# TinyDVR_Slave.net
KiCad netlist of a schematic drawn in Altium Designer
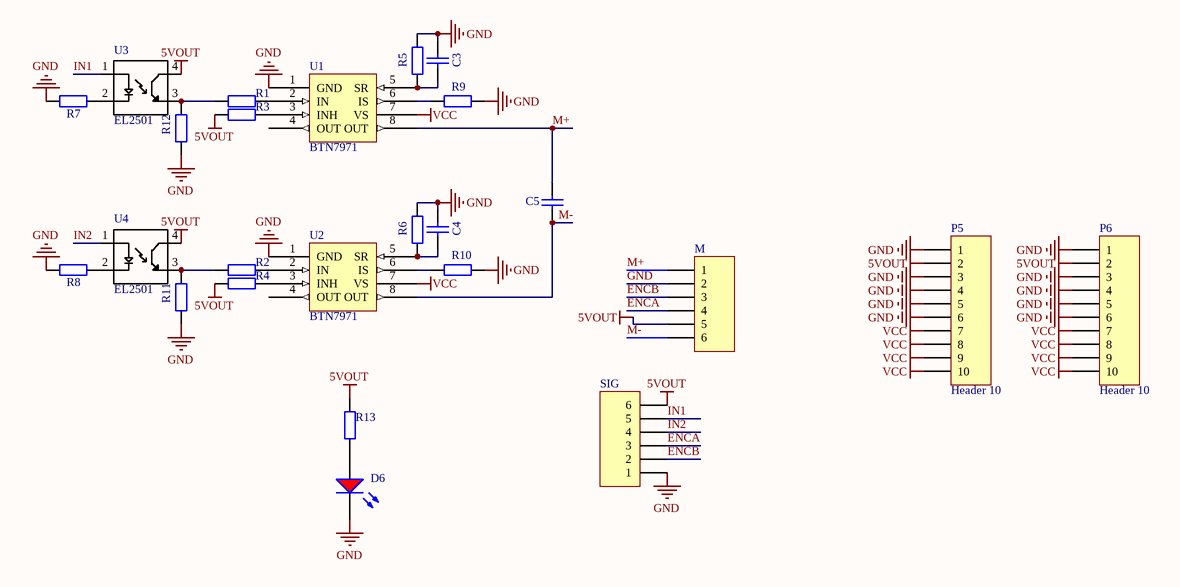
[diagram p0: TinyDVR_Slave.SchDoc]

(export (version "E")
  (design (tool "Eeschema 10.0.6"))
  (components
    (comp (ref "C3")
      (value "100nF (104) 10% 50V")
      (footprint "0603_C")
      (description "贴片电容")
      (libsource (lib "Miscellaneous Devices LC") (part "0603 100nF (104) 10% 50V"))
    )
    (comp (ref "C4")
      (value "100nF (104) 10% 50V")
      (footprint "0603_C")
      (description "贴片电容")
      (libsource (lib "Miscellaneous Devices LC") (part "0603 100nF (104) 10% 50V"))
    )
    (comp (ref "C5")
      (value "22pF (220) 5% 50V")
      (footprint "0603_C")
      (description "贴片电容")
      (libsource (lib "Miscellaneous Devices LC") (part "0603 22pF (220) 5% 50V"))
    )
    (comp (ref "D6")
      (value "红灯 0603")
      (footprint "0603_LED_S1")
      (description "发光二极管")
      (libsource (lib "Miscellaneous Devices LC") (part "0603 红灯"))
    )
    (comp (ref "M")
      (value "Header 6H")
      (footprint "HDR1X6H")
      (description "Header, 6-Pin, Right Angle")
      (fields (field (name "PUBLISHER") "Altium Limited"))
      (libsource (lib "Miscellaneous Connectors") (part "Header 6H"))
    )
    (comp (ref "P5")
      (value "Header 10")
      (footprint "HDR1X10")
      (description "Header, 10-Pin")
      (fields (field (name "PUBLISHER") "Altium Limited"))
      (libsource (lib "Miscellaneous Connectors") (part "Header 10"))
    )
    (comp (ref "P6")
      (value "Header 10")
      (footprint "HDR1X10")
      (description "Header, 10-Pin")
      (fields (field (name "PUBLISHER") "Altium Limited"))
      (libsource (lib "Miscellaneous Connectors") (part "Header 10"))
    )
    (comp (ref "R1")
      (value "10KΩ (1002) ±1%")
      (footprint "0603_R")
      (description "贴片电阻")
      (libsource (lib "Miscellaneous Devices LC") (part "0603 10KΩ (1002) 1%"))
    )
    (comp (ref "R2")
      (value "10KΩ (1002) ±1%")
      (footprint "0603_R")
      (description "贴片电阻")
      (libsource (lib "Miscellaneous Devices LC") (part "0603 10KΩ (1002) 1%"))
    )
    (comp (ref "R3")
      (value "10KΩ (1002) ±1%")
      (footprint "0603_R")
      (description "贴片电阻")
      (libsource (lib "Miscellaneous Devices LC") (part "0603 10KΩ (1002) 1%"))
    )
    (comp (ref "R4")
      (value "10KΩ (1002) ±1%")
      (footprint "0603_R")
      (description "贴片电阻")
      (libsource (lib "Miscellaneous Devices LC") (part "0603 10KΩ (1002) 1%"))
    )
    (comp (ref "R5")
      (value "1KΩ (1001) ±1%")
      (footprint "0603_R")
      (description "贴片电阻")
      (libsource (lib "") (part "0603 1KΩ (1001) 1%_1"))
    )
    (comp (ref "R6")
      (value "1KΩ (1001) ±1%")
      (footprint "0603_R")
      (description "贴片电阻")
      (libsource (lib "") (part "0603 1KΩ (1001) 1%_1"))
    )
    (comp (ref "R7")
      (value "1KΩ (1001) ±1%")
      (footprint "0603_R")
      (description "贴片电阻")
      (libsource (lib "Miscellaneous Devices LC") (part "0603 1KΩ (1001) 1%"))
    )
    (comp (ref "R8")
      (value "1KΩ (1001) ±1%")
      (footprint "0603_R")
      (description "贴片电阻")
      (libsource (lib "Miscellaneous Devices LC") (part "0603 1KΩ (1001) 1%"))
    )
    (comp (ref "R9")
      (value "2KΩ (2001) ±1%")
      (footprint "0603_R")
      (description "贴片电阻")
      (libsource (lib "") (part "0603 2KΩ (2001) 1%_1"))
    )
    (comp (ref "R10")
      (value "2KΩ (2001) ±1%")
      (footprint "0603_R")
      (description "贴片电阻")
      (libsource (lib "") (part "0603 2KΩ (2001) 1%_1"))
    )
    (comp (ref "R11")
      (value "2KΩ (2001) ±1%")
      (footprint "0603_R")
      (description "贴片电阻")
      (libsource (lib "Miscellaneous Devices LC") (part "0603 2KΩ (2001) 1%"))
    )
    (comp (ref "R12")
      (value "2KΩ (2001) ±1%")
      (footprint "0603_R")
      (description "贴片电阻")
      (libsource (lib "Miscellaneous Devices LC") (part "0603 2KΩ (2001) 1%"))
    )
    (comp (ref "R13")
      (value "4.7k")
      (footprint "0603_R")
      (description "贴片电阻")
      (libsource (lib "Miscellaneous Devices LC") (part "0603 470Ω (4700) 1%"))
    )
    (comp (ref "SIG")
      (value "Header 6H")
      (footprint "HDR1X6H")
      (description "Header, 6-Pin, Right Angle")
      (fields (field (name "PUBLISHER") "Altium Limited"))
      (libsource (lib "") (part "Header 6H_1"))
    )
    (comp (ref "U1")
      (value "BTN7971")
      (footprint "DPAK127P1615X127-8N")
      (libsource (lib "Sheet2") (part "BTN7971"))
    )
    (comp (ref "U2")
      (value "BTN7971")
      (footprint "DPAK127P1615X127-8N")
      (libsource (lib "Sheet2") (part "BTN7971"))
    )
    (comp (ref "U3")
      (value "EL2501")
      (footprint "*SOIC254P1030X390-4N_EL817S1(A)(TU)-V")
      (description "Optoisoltr 5kv Transistor 4-Smd")
      (fields (field (name "MF") "Everlight Electronics") (field (name "MP") "EL817S1_A__TU_-V"))
      (libsource (lib "altium-import") (part "root_0_EL817S1(A)(TU)-V_"))
    )
    (comp (ref "U4")
      (value "EL2501")
      (footprint "*SOIC254P1030X390-4N_EL817S1(A)(TU)-V")
      (description "Optoisoltr 5kv Transistor 4-Smd")
      (fields (field (name "MF") "Everlight Electronics") (field (name "MP") "EL817S1_A__TU_-V"))
      (libsource (lib "altium-import") (part "root_0_EL817S1(A)(TU)-V_"))
    )
  )
  (nets
    (net (code "1") (name "/ENCA") (class "Default")
      (node (ref "M") (pin "4") (pinfunction "4_4") (pintype "passive"))
      (node (ref "SIG") (pin "3") (pinfunction "3_3") (pintype "passive"))
    )
    (net (code "2") (name "/ENCB") (class "Default")
      (node (ref "M") (pin "3") (pinfunction "3_3") (pintype "passive"))
      (node (ref "SIG") (pin "2") (pinfunction "2_2") (pintype "passive"))
    )
    (net (code "3") (name "/IN1") (class "Default")
      (node (ref "SIG") (pin "5") (pinfunction "5_5") (pintype "passive"))
      (node (ref "U3") (pin "1") (pinfunction "A_1") (pintype "passive"))
    )
    (net (code "4") (name "/IN2") (class "Default")
      (node (ref "SIG") (pin "4") (pinfunction "4_4") (pintype "passive"))
      (node (ref "U4") (pin "1") (pinfunction "A_1") (pintype "passive"))
    )
    (net (code "5") (name "/M+") (class "Default")
      (node (ref "C5") (pin "2") (pinfunction "2_2") (pintype "passive"))
      (node (ref "M") (pin "1") (pinfunction "1_1") (pintype "passive"))
      (node (ref "U1") (pin "8") (pinfunction "OUT_8") (pintype "output"))
    )
    (net (code "6") (name "/M-") (class "Default")
      (node (ref "C5") (pin "1") (pinfunction "1_1") (pintype "passive"))
      (node (ref "M") (pin "6") (pinfunction "6_6") (pintype "passive"))
      (node (ref "U2") (pin "8") (pinfunction "OUT_8") (pintype "output"))
    )
    (net (code "7") (name "5VOUT") (class "Default")
      (node (ref "M") (pin "5") (pinfunction "5_5") (pintype "passive"))
      (node (ref "P5") (pin "2") (pinfunction "2_2") (pintype "passive"))
      (node (ref "P6") (pin "2") (pinfunction "2_2") (pintype "passive"))
      (node (ref "R13") (pin "2") (pinfunction "2_2") (pintype "passive"))
      (node (ref "R3") (pin "1") (pinfunction "1_1") (pintype "passive"))
      (node (ref "R4") (pin "1") (pinfunction "1_1") (pintype "passive"))
      (node (ref "SIG") (pin "6") (pinfunction "6_6") (pintype "passive"))
      (node (ref "U3") (pin "4") (pinfunction "CT_4") (pintype "passive"))
      (node (ref "U4") (pin "4") (pinfunction "CT_4") (pintype "passive"))
    )
    (net (code "8") (name "GND") (class "Default")
      (node (ref "C3") (pin "2") (pinfunction "2_2") (pintype "passive"))
      (node (ref "C4") (pin "2") (pinfunction "2_2") (pintype "passive"))
      (node (ref "D6") (pin "K") (pinfunction "K_K") (pintype "passive"))
      (node (ref "M") (pin "2") (pinfunction "2_2") (pintype "passive"))
      (node (ref "P5") (pin "1") (pinfunction "1_1") (pintype "passive"))
      (node (ref "P5") (pin "3") (pinfunction "3_3") (pintype "passive"))
      (node (ref "P5") (pin "4") (pinfunction "4_4") (pintype "passive"))
      (node (ref "P5") (pin "5") (pinfunction "5_5") (pintype "passive"))
      (node (ref "P5") (pin "6") (pinfunction "6_6") (pintype "passive"))
      (node (ref "P6") (pin "1") (pinfunction "1_1") (pintype "passive"))
      (node (ref "P6") (pin "3") (pinfunction "3_3") (pintype "passive"))
      (node (ref "P6") (pin "4") (pinfunction "4_4") (pintype "passive"))
      (node (ref "P6") (pin "5") (pinfunction "5_5") (pintype "passive"))
      (node (ref "P6") (pin "6") (pinfunction "6_6") (pintype "passive"))
      (node (ref "R10") (pin "1") (pinfunction "1_1") (pintype "passive"))
      (node (ref "R11") (pin "1") (pinfunction "1_1") (pintype "passive"))
      (node (ref "R12") (pin "1") (pinfunction "1_1") (pintype "passive"))
      (node (ref "R5") (pin "2") (pinfunction "2_2") (pintype "passive"))
      (node (ref "R6") (pin "2") (pinfunction "2_2") (pintype "passive"))
      (node (ref "R7") (pin "2") (pinfunction "2_2") (pintype "passive"))
      (node (ref "R8") (pin "2") (pinfunction "2_2") (pintype "passive"))
      (node (ref "R9") (pin "1") (pinfunction "1_1") (pintype "passive"))
      (node (ref "SIG") (pin "1") (pinfunction "1_1") (pintype "passive"))
      (node (ref "U1") (pin "1") (pinfunction "GND_1") (pintype "passive"))
      (node (ref "U2") (pin "1") (pinfunction "GND_1") (pintype "passive"))
    )
    (net (code "9") (name "Net-(D6-PadA)") (class "Default")
      (node (ref "D6") (pin "A") (pinfunction "A_A") (pintype "passive"))
      (node (ref "R13") (pin "1") (pinfunction "1_1") (pintype "passive"))
    )
    (net (code "10") (name "Net-(U1-IN)") (class "Default")
      (node (ref "R1") (pin "2") (pinfunction "2_2") (pintype "passive"))
      (node (ref "U1") (pin "2") (pinfunction "IN_2") (pintype "input"))
    )
    (net (code "11") (name "Net-(U1-INH)") (class "Default")
      (node (ref "R3") (pin "2") (pinfunction "2_2") (pintype "passive"))
      (node (ref "U1") (pin "3") (pinfunction "INH_3") (pintype "input"))
    )
    (net (code "12") (name "Net-(U1-IS)") (class "Default")
      (node (ref "R9") (pin "2") (pinfunction "2_2") (pintype "passive"))
      (node (ref "U1") (pin "6") (pinfunction "IS_6") (pintype "output"))
    )
    (net (code "13") (name "Net-(U1-SR)") (class "Default")
      (node (ref "C3") (pin "1") (pinfunction "1_1") (pintype "passive"))
      (node (ref "R5") (pin "1") (pinfunction "1_1") (pintype "passive"))
      (node (ref "U1") (pin "5") (pinfunction "SR_5") (pintype "input"))
    )
    (net (code "14") (name "Net-(U2-IN)") (class "Default")
      (node (ref "R2") (pin "2") (pinfunction "2_2") (pintype "passive"))
      (node (ref "U2") (pin "2") (pinfunction "IN_2") (pintype "input"))
    )
    (net (code "15") (name "Net-(U2-INH)") (class "Default")
      (node (ref "R4") (pin "2") (pinfunction "2_2") (pintype "passive"))
      (node (ref "U2") (pin "3") (pinfunction "INH_3") (pintype "input"))
    )
    (net (code "16") (name "Net-(U2-IS)") (class "Default")
      (node (ref "R10") (pin "2") (pinfunction "2_2") (pintype "passive"))
      (node (ref "U2") (pin "6") (pinfunction "IS_6") (pintype "output"))
    )
    (net (code "17") (name "Net-(U2-SR)") (class "Default")
      (node (ref "C4") (pin "1") (pinfunction "1_1") (pintype "passive"))
      (node (ref "R6") (pin "1") (pinfunction "1_1") (pintype "passive"))
      (node (ref "U2") (pin "5") (pinfunction "SR_5") (pintype "input"))
    )
    (net (code "18") (name "Net-(U3-C)") (class "Default")
      (node (ref "R7") (pin "1") (pinfunction "1_1") (pintype "passive"))
      (node (ref "U3") (pin "2") (pinfunction "C_2") (pintype "passive"))
    )
    (net (code "19") (name "Net-(U3-ET)") (class "Default")
      (node (ref "R1") (pin "1") (pinfunction "1_1") (pintype "passive"))
      (node (ref "R12") (pin "2") (pinfunction "2_2") (pintype "passive"))
      (node (ref "U3") (pin "3") (pinfunction "ET_3") (pintype "passive"))
    )
    (net (code "20") (name "Net-(U4-C)") (class "Default")
      (node (ref "R8") (pin "1") (pinfunction "1_1") (pintype "passive"))
      (node (ref "U4") (pin "2") (pinfunction "C_2") (pintype "passive"))
    )
    (net (code "21") (name "Net-(U4-ET)") (class "Default")
      (node (ref "R11") (pin "2") (pinfunction "2_2") (pintype "passive"))
      (node (ref "R2") (pin "1") (pinfunction "1_1") (pintype "passive"))
      (node (ref "U4") (pin "3") (pinfunction "ET_3") (pintype "passive"))
    )
    (net (code "22") (name "VCC") (class "Default")
      (node (ref "P5") (pin "10") (pinfunction "10_10") (pintype "passive"))
      (node (ref "P5") (pin "7") (pinfunction "7_7") (pintype "passive"))
      (node (ref "P5") (pin "8") (pinfunction "8_8") (pintype "passive"))
      (node (ref "P5") (pin "9") (pinfunction "9_9") (pintype "passive"))
      (node (ref "P6") (pin "10") (pinfunction "10_10") (pintype "passive"))
      (node (ref "P6") (pin "7") (pinfunction "7_7") (pintype "passive"))
      (node (ref "P6") (pin "8") (pinfunction "8_8") (pintype "passive"))
      (node (ref "P6") (pin "9") (pinfunction "9_9") (pintype "passive"))
      (node (ref "U1") (pin "7") (pinfunction "VS_7") (pintype "passive"))
      (node (ref "U2") (pin "7") (pinfunction "VS_7") (pintype "passive"))
    )
    (net (code "23") (name "unconnected-(U1-OUT-Pad4)") (class "Default")
      (node (ref "U1") (pin "4") (pinfunction "OUT_4") (pintype "output"))
    )
    (net (code "24") (name "unconnected-(U2-OUT-Pad4)") (class "Default")
      (node (ref "U2") (pin "4") (pinfunction "OUT_4") (pintype "output"))
    )
  )
)
